# arduino_Uno_mod.net
KiCad netlist of a schematic drawn in EAGLE
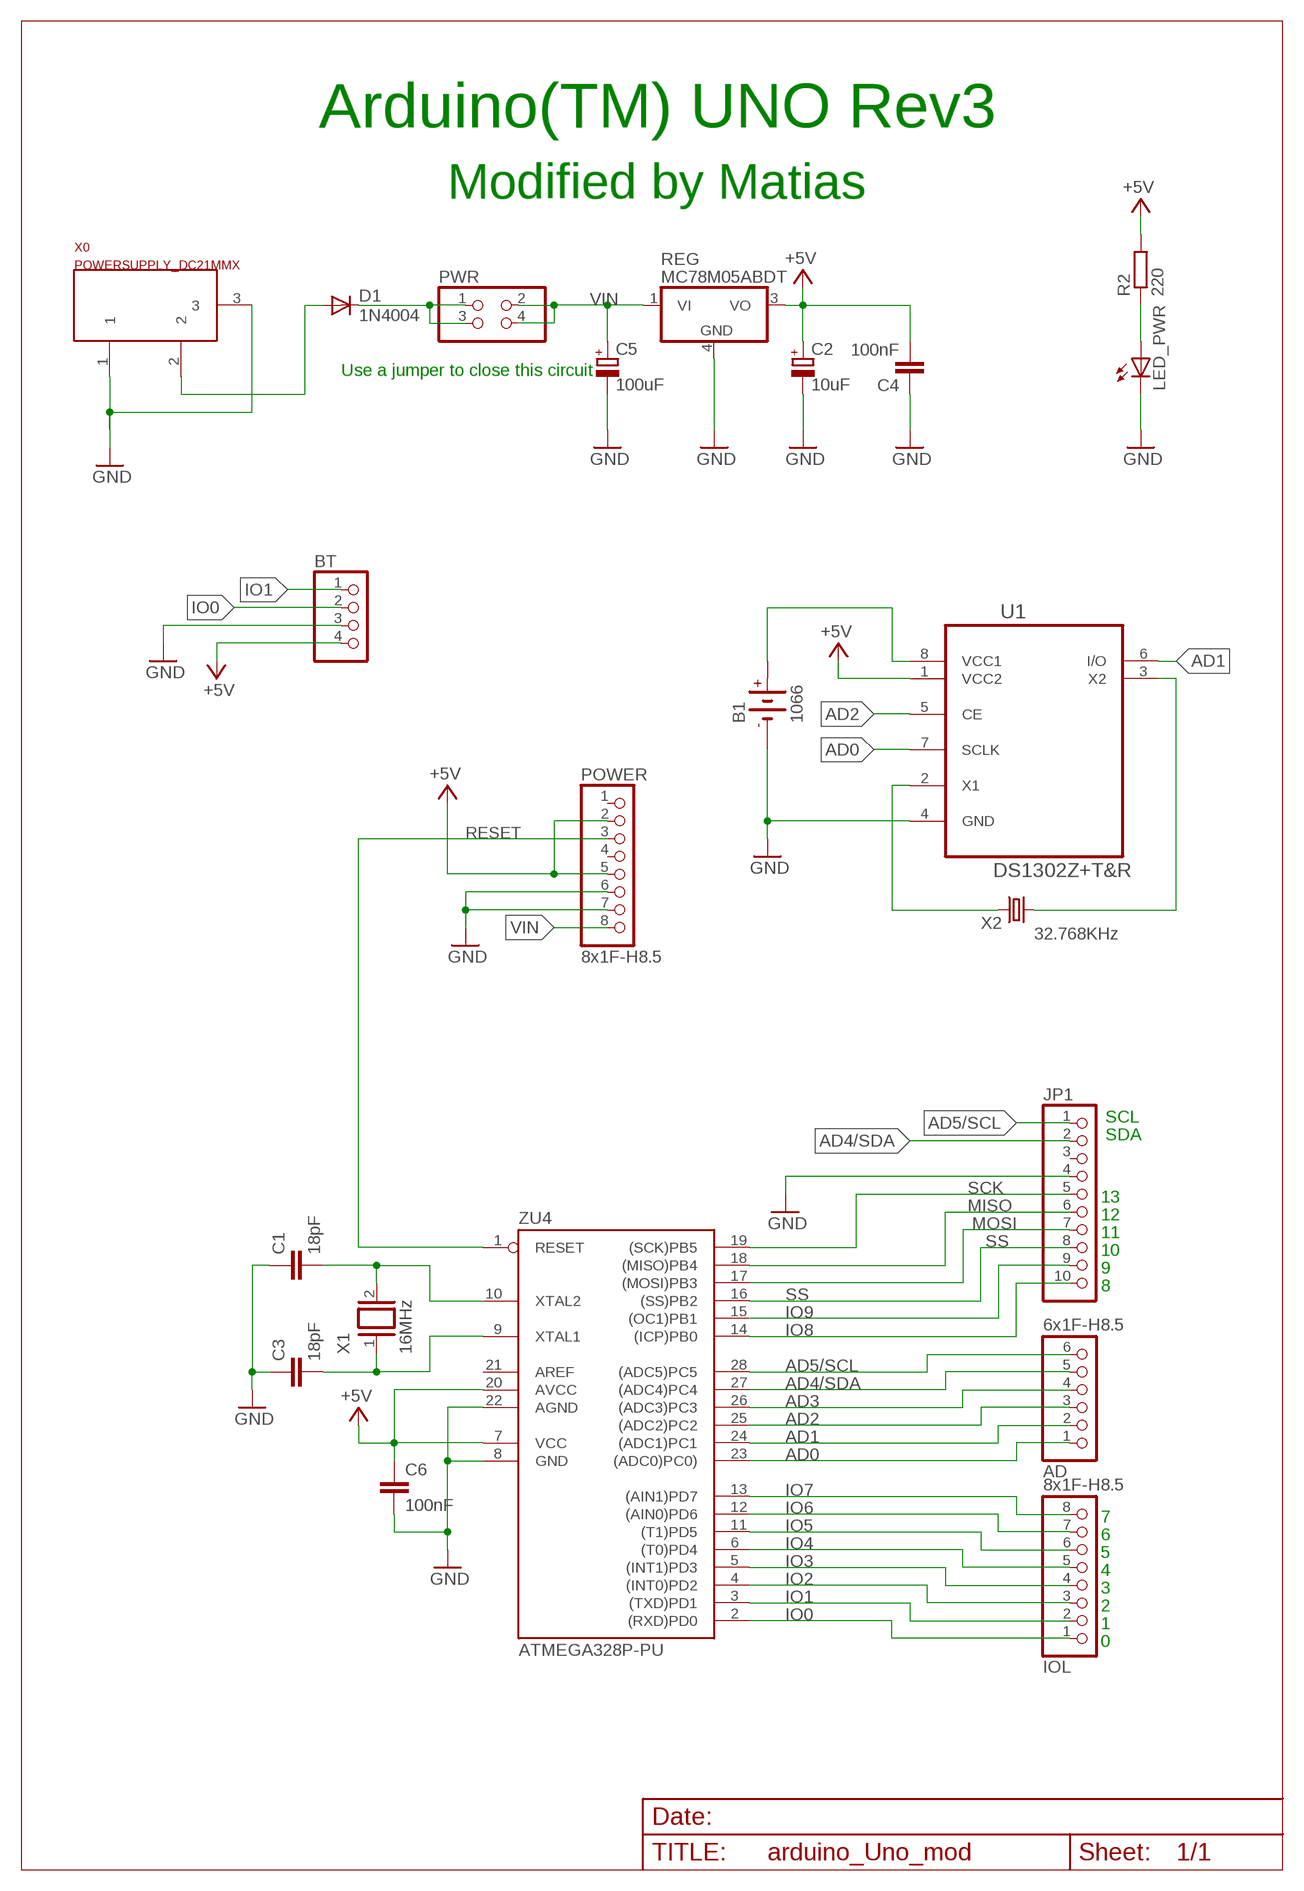
[diagram p0: schematic, sheet 1]

(export (version "E")
  (design (tool "Eeschema 10.0.6"))
  (components
    (comp (ref "AD")
      (value "6x1F-H8.5")
      (footprint "eagle-import:1X06")
      (libsource (lib "eagle-import") (part "PINHD-1X6"))
    )
    (comp (ref "B1")
      (value "1066")
      (footprint "eagle-import:1066")
      (fields (field (name "MF") "Greenlee Communications"))
      (libsource (lib "eagle-import") (part "1066"))
    )
    (comp (ref "BT")
      (value "PINHD-1X4/90")
      (footprint "eagle-import:1X04_90")
      (libsource (lib "eagle-import") (part "PINHD-1X4/90"))
    )
    (comp (ref "C1")
      (value "18pF")
      (footprint "eagle-import:C025-025X050")
      (libsource (lib "eagle-import") (part "C-EU025-025X050"))
    )
    (comp (ref "C2")
      (value "10uF")
      (footprint "eagle-import:E2,5-5")
      (libsource (lib "eagle-import") (part "CPOL-EUE2.5-5"))
    )
    (comp (ref "C3")
      (value "18pF")
      (footprint "eagle-import:C025-025X050")
      (libsource (lib "eagle-import") (part "C-EU025-025X050"))
    )
    (comp (ref "C4")
      (value "100nF")
      (footprint "eagle-import:C025-025X050")
      (libsource (lib "eagle-import") (part "C-EU025-025X050"))
    )
    (comp (ref "C5")
      (value "100uF")
      (footprint "eagle-import:E2-5")
      (libsource (lib "eagle-import") (part "rcl_334_CPOL-EUE2-5"))
    )
    (comp (ref "C6")
      (value "100nF")
      (footprint "eagle-import:C025-025X050")
      (libsource (lib "eagle-import") (part "C-EU025-025X050"))
    )
    (comp (ref "D1")
      (value "1N4004")
      (footprint "eagle-import:DO41-10")
      (libsource (lib "eagle-import") (part "1N4004"))
    )
    (comp (ref "IOL")
      (value "8x1F-H8.5")
      (footprint "eagle-import:1X08")
      (libsource (lib "eagle-import") (part "PINHD-1X8"))
    )
    (comp (ref "JP1")
      (value "PINHD-1X10")
      (footprint "eagle-import:1X10")
      (libsource (lib "eagle-import") (part "PINHD-1X10"))
    )
    (comp (ref "LED_PWR")
      (value "LED3MM")
      (footprint "eagle-import:LED3MM")
      (libsource (lib "eagle-import") (part "LED3MM"))
    )
    (comp (ref "POWER")
      (value "8x1F-H8.5")
      (footprint "eagle-import:1X08")
      (libsource (lib "eagle-import") (part "PINHD-1X8"))
    )
    (comp (ref "PWR")
      (value "PINHD-2X2")
      (footprint "eagle-import:2X02")
      (libsource (lib "eagle-import") (part "PINHD-2X2"))
    )
    (comp (ref "R2")
      (value "220")
      (footprint "eagle-import:R1206")
      (libsource (lib "eagle-import") (part "R-EU_R1206"))
    )
    (comp (ref "REG")
      (value "MC78M05ABDT")
      (footprint "eagle-import:DPACK_3")
      (libsource (lib "eagle-import") (part "MC78M05ABDT"))
    )
    (comp (ref "U1")
      (value "DS1302Z+T&R")
      (footprint "eagle-import:SOIC127P600X175-8N")
      (fields (field (name "MF") "Maxim Integrated") (field (name "MP") "DS1302Z+T&amp;R"))
      (libsource (lib "eagle-import") (part "DS1302Z+T&R"))
    )
    (comp (ref "X0")
      (value "POWERSUPPLY_DC21MMX")
      (footprint "eagle-import:POWERSUPPLY_DC-21MM")
      (libsource (lib "eagle-import") (part "POWERSUPPLY_DC21MMX"))
    )
    (comp (ref "X1")
      (value "16MHz")
      (footprint "eagle-import:QS")
      (libsource (lib "eagle-import") (part "XTAL/S"))
    )
    (comp (ref "X2")
      (value "32.768KHz")
      (footprint "eagle-import:WATCH-3X8")
      (libsource (lib "eagle-import") (part "CRYSTALS-NOGND-WATCH-3X8"))
    )
    (comp (ref "ZU4")
      (value "ATMEGA328P-PU")
      (footprint "eagle-import:DIL28-3")
      (libsource (lib "eagle-import") (part "ATMEGA328P-PU"))
    )
  )
  (nets
    (net (code "1") (name "+5V") (class "Default")
      (node (ref "BT") (pin "4") (pinfunction "4_4") (pintype "passive"))
      (node (ref "C2") (pin "+") (pinfunction "+_+") (pintype "passive"))
      (node (ref "C4") (pin "2") (pinfunction "2_2") (pintype "passive"))
      (node (ref "C6") (pin "1") (pinfunction "1_1") (pintype "passive"))
      (node (ref "POWER") (pin "2") (pinfunction "2_2") (pintype "passive"))
      (node (ref "POWER") (pin "5") (pinfunction "5_5") (pintype "passive"))
      (node (ref "R2") (pin "2") (pinfunction "2_2") (pintype "passive"))
      (node (ref "REG") (pin "3") (pinfunction "VO_3") (pintype "passive"))
      (node (ref "U1") (pin "1") (pinfunction "VCC2_1") (pintype "power_in"))
      (node (ref "ZU4") (pin "20") (pinfunction "AVCC_20") (pintype "power_in"))
      (node (ref "ZU4") (pin "7") (pinfunction "VCC_7") (pintype "power_in"))
    )
    (net (code "2") (name "/AD3") (class "Default")
      (node (ref "AD") (pin "4") (pinfunction "4_4") (pintype "passive"))
      (node (ref "ZU4") (pin "26") (pinfunction "(ADC3)PC3_26") (pintype "bidirectional"))
    )
    (net (code "3") (name "/IO2") (class "Default")
      (node (ref "IOL") (pin "3") (pinfunction "3_3") (pintype "passive"))
      (node (ref "ZU4") (pin "4") (pinfunction "(INT0)PD2_4") (pintype "bidirectional"))
    )
    (net (code "4") (name "/IO3") (class "Default")
      (node (ref "IOL") (pin "4") (pinfunction "4_4") (pintype "passive"))
      (node (ref "ZU4") (pin "5") (pinfunction "(INT1)PD3_5") (pintype "bidirectional"))
    )
    (net (code "5") (name "/IO4") (class "Default")
      (node (ref "IOL") (pin "5") (pinfunction "5_5") (pintype "passive"))
      (node (ref "ZU4") (pin "6") (pinfunction "(T0)PD4_6") (pintype "bidirectional"))
    )
    (net (code "6") (name "/IO5") (class "Default")
      (node (ref "IOL") (pin "6") (pinfunction "6_6") (pintype "passive"))
      (node (ref "ZU4") (pin "11") (pinfunction "(T1)PD5_11") (pintype "bidirectional"))
    )
    (net (code "7") (name "/IO6") (class "Default")
      (node (ref "IOL") (pin "7") (pinfunction "7_7") (pintype "passive"))
      (node (ref "ZU4") (pin "12") (pinfunction "(AIN0)PD6_12") (pintype "bidirectional"))
    )
    (net (code "8") (name "/IO7") (class "Default")
      (node (ref "IOL") (pin "8") (pinfunction "8_8") (pintype "passive"))
      (node (ref "ZU4") (pin "13") (pinfunction "(AIN1)PD7_13") (pintype "bidirectional"))
    )
    (net (code "9") (name "/IO8") (class "Default")
      (node (ref "JP1") (pin "10") (pinfunction "10_10") (pintype "passive"))
      (node (ref "ZU4") (pin "14") (pinfunction "(ICP)PB0_14") (pintype "bidirectional"))
    )
    (net (code "10") (name "/IO9") (class "Default")
      (node (ref "JP1") (pin "9") (pinfunction "9_9") (pintype "passive"))
      (node (ref "ZU4") (pin "15") (pinfunction "(OC1)PB1_15") (pintype "bidirectional"))
    )
    (net (code "11") (name "/MISO") (class "Default")
      (node (ref "JP1") (pin "6") (pinfunction "6_6") (pintype "passive"))
      (node (ref "ZU4") (pin "18") (pinfunction "(MISO)PB4_18") (pintype "bidirectional"))
    )
    (net (code "12") (name "/MOSI") (class "Default")
      (node (ref "JP1") (pin "7") (pinfunction "7_7") (pintype "passive"))
      (node (ref "ZU4") (pin "17") (pinfunction "(MOSI)PB3_17") (pintype "bidirectional"))
    )
    (net (code "13") (name "/RESET") (class "Default")
      (node (ref "POWER") (pin "3") (pinfunction "3_3") (pintype "passive"))
      (node (ref "ZU4") (pin "1") (pinfunction "RESET_1") (pintype "input"))
    )
    (net (code "14") (name "/SCK") (class "Default")
      (node (ref "JP1") (pin "5") (pinfunction "5_5") (pintype "passive"))
      (node (ref "ZU4") (pin "19") (pinfunction "(SCK)PB5_19") (pintype "bidirectional"))
    )
    (net (code "15") (name "/SS") (class "Default")
      (node (ref "JP1") (pin "8") (pinfunction "8_8") (pintype "passive"))
      (node (ref "ZU4") (pin "16") (pinfunction "(SS)PB2_16") (pintype "bidirectional"))
    )
    (net (code "16") (name "AD0") (class "Default")
      (node (ref "AD") (pin "1") (pinfunction "1_1") (pintype "passive"))
      (node (ref "U1") (pin "7") (pinfunction "SCLK_7") (pintype "input"))
      (node (ref "ZU4") (pin "23") (pinfunction "(ADC0)PC0)_23") (pintype "bidirectional"))
    )
    (net (code "17") (name "AD1") (class "Default")
      (node (ref "AD") (pin "2") (pinfunction "2_2") (pintype "passive"))
      (node (ref "U1") (pin "6") (pinfunction "I/O_6") (pintype "bidirectional"))
      (node (ref "ZU4") (pin "24") (pinfunction "(ADC1)PC1_24") (pintype "bidirectional"))
    )
    (net (code "18") (name "AD2") (class "Default")
      (node (ref "AD") (pin "3") (pinfunction "3_3") (pintype "passive"))
      (node (ref "U1") (pin "5") (pinfunction "CE_5") (pintype "input"))
      (node (ref "ZU4") (pin "25") (pinfunction "(ADC2)PC2_25") (pintype "bidirectional"))
    )
    (net (code "19") (name "AD4{slash}SDA") (class "Default")
      (node (ref "AD") (pin "5") (pinfunction "5_5") (pintype "passive"))
      (node (ref "JP1") (pin "2") (pinfunction "2_2") (pintype "passive"))
      (node (ref "ZU4") (pin "27") (pinfunction "(ADC4)PC4_27") (pintype "bidirectional"))
    )
    (net (code "20") (name "AD5{slash}SCL") (class "Default")
      (node (ref "AD") (pin "6") (pinfunction "6_6") (pintype "passive"))
      (node (ref "JP1") (pin "1") (pinfunction "1_1") (pintype "passive"))
      (node (ref "ZU4") (pin "28") (pinfunction "(ADC5)PC5_28") (pintype "bidirectional"))
    )
    (net (code "21") (name "GND") (class "Default")
      (node (ref "B1") (pin "-") (pinfunction "-_-") (pintype "passive"))
      (node (ref "BT") (pin "3") (pinfunction "3_3") (pintype "passive"))
      (node (ref "C1") (pin "1") (pinfunction "1_1") (pintype "passive"))
      (node (ref "C2") (pin "-") (pinfunction "-_-") (pintype "passive"))
      (node (ref "C3") (pin "1") (pinfunction "1_1") (pintype "passive"))
      (node (ref "C4") (pin "1") (pinfunction "1_1") (pintype "passive"))
      (node (ref "C5") (pin "-") (pinfunction "-_-") (pintype "passive"))
      (node (ref "C6") (pin "2") (pinfunction "2_2") (pintype "passive"))
      (node (ref "JP1") (pin "4") (pinfunction "4_4") (pintype "passive"))
      (node (ref "LED_PWR") (pin "K") (pinfunction "C_K") (pintype "passive"))
      (node (ref "POWER") (pin "6") (pinfunction "6_6") (pintype "passive"))
      (node (ref "POWER") (pin "7") (pinfunction "7_7") (pintype "passive"))
      (node (ref "REG") (pin "4") (pinfunction "GND_4") (pintype "passive"))
      (node (ref "U1") (pin "4") (pinfunction "GND_4") (pintype "passive"))
      (node (ref "X0") (pin "1") (pinfunction "1_1") (pintype "power_in"))
      (node (ref "X0") (pin "3") (pinfunction "3_3") (pintype "power_in"))
      (node (ref "ZU4") (pin "22") (pinfunction "AGND_22") (pintype "power_in"))
      (node (ref "ZU4") (pin "8") (pinfunction "GND_8") (pintype "power_in"))
    )
    (net (code "22") (name "IO0") (class "Default")
      (node (ref "BT") (pin "2") (pinfunction "2_2") (pintype "passive"))
      (node (ref "IOL") (pin "1") (pinfunction "1_1") (pintype "passive"))
      (node (ref "ZU4") (pin "2") (pinfunction "(RXD)PD0_2") (pintype "bidirectional"))
    )
    (net (code "23") (name "IO1") (class "Default")
      (node (ref "BT") (pin "1") (pinfunction "1_1") (pintype "passive"))
      (node (ref "IOL") (pin "2") (pinfunction "2_2") (pintype "passive"))
      (node (ref "ZU4") (pin "3") (pinfunction "(TXD)PD1_3") (pintype "bidirectional"))
    )
    (net (code "24") (name "Net-(D1-PadA)") (class "Default")
      (node (ref "D1") (pin "A") (pinfunction "A_A") (pintype "passive"))
      (node (ref "X0") (pin "2") (pinfunction "2_2") (pintype "power_in"))
    )
    (net (code "25") (name "Net-(D1-PadC)") (class "Default")
      (node (ref "D1") (pin "C") (pinfunction "C_C") (pintype "passive"))
      (node (ref "PWR") (pin "1") (pinfunction "1_1") (pintype "passive"))
      (node (ref "PWR") (pin "3") (pinfunction "3_3") (pintype "passive"))
    )
    (net (code "26") (name "Net-(LED_PWR-PadA)") (class "Default")
      (node (ref "LED_PWR") (pin "A") (pinfunction "A_A") (pintype "passive"))
      (node (ref "R2") (pin "1") (pinfunction "1_1") (pintype "passive"))
    )
    (net (code "27") (name "Net-(U1-VCC1)") (class "Default")
      (node (ref "B1") (pin "+") (pinfunction "+_+") (pintype "passive"))
      (node (ref "U1") (pin "8") (pinfunction "VCC1_8") (pintype "power_in"))
    )
    (net (code "28") (name "Net-(U1-X1)") (class "Default")
      (node (ref "U1") (pin "2") (pinfunction "X1_2") (pintype "input"))
      (node (ref "X2") (pin "2") (pinfunction "2_2") (pintype "passive"))
    )
    (net (code "29") (name "Net-(U1-X2)") (class "Default")
      (node (ref "U1") (pin "3") (pinfunction "X2_3") (pintype "output"))
      (node (ref "X2") (pin "1") (pinfunction "1_1") (pintype "passive"))
    )
    (net (code "30") (name "Net-(ZU4-XTAL1)") (class "Default")
      (node (ref "C3") (pin "2") (pinfunction "2_2") (pintype "passive"))
      (node (ref "X1") (pin "1") (pinfunction "1_1") (pintype "passive"))
      (node (ref "ZU4") (pin "9") (pinfunction "XTAL1_9") (pintype "bidirectional"))
    )
    (net (code "31") (name "Net-(ZU4-XTAL2)") (class "Default")
      (node (ref "C1") (pin "2") (pinfunction "2_2") (pintype "passive"))
      (node (ref "X1") (pin "2") (pinfunction "2_2") (pintype "passive"))
      (node (ref "ZU4") (pin "10") (pinfunction "XTAL2_10") (pintype "bidirectional"))
    )
    (net (code "32") (name "VIN") (class "Default")
      (node (ref "C5") (pin "+") (pinfunction "+_+") (pintype "passive"))
      (node (ref "POWER") (pin "8") (pinfunction "8_8") (pintype "passive"))
      (node (ref "PWR") (pin "2") (pinfunction "2_2") (pintype "passive"))
      (node (ref "PWR") (pin "4") (pinfunction "4_4") (pintype "passive"))
      (node (ref "REG") (pin "1") (pinfunction "VI_1") (pintype "input"))
    )
    (net (code "33") (name "unconnected-(JP1-Pad3)") (class "Default")
      (node (ref "JP1") (pin "3") (pinfunction "3_3") (pintype "passive"))
    )
    (net (code "34") (name "unconnected-(POWER-Pad1)") (class "Default")
      (node (ref "POWER") (pin "1") (pinfunction "1_1") (pintype "passive"))
    )
    (net (code "35") (name "unconnected-(POWER-Pad4)") (class "Default")
      (node (ref "POWER") (pin "4") (pinfunction "4_4") (pintype "passive"))
    )
    (net (code "36") (name "unconnected-(ZU4-AREF-Pad21)") (class "Default")
      (node (ref "ZU4") (pin "21") (pinfunction "AREF_21") (pintype "passive"))
    )
  )
)
